# Pre_Amplifier.net
KiCad netlist of a schematic drawn in Altium Designer
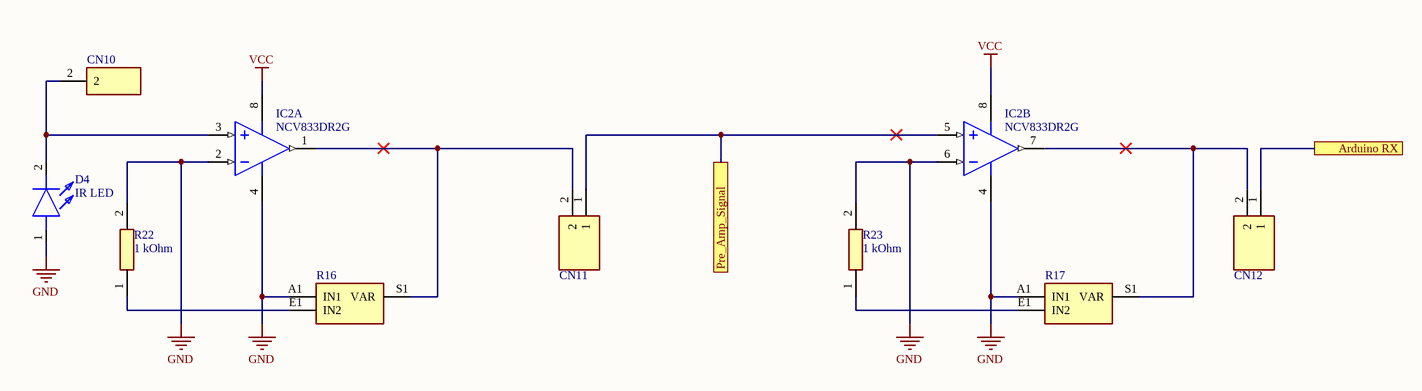
[diagram p0: Pre_Amplifier.SchDoc]

(export (version "E")
  (design (tool "Eeschema 10.0.6"))
  (components
    (comp (ref "CN10")
      (value "1 Pin Header")
      (footprint "1 PIN HEADER")
      (description "Connector")
      (fields
        (field (name "MANUFACTURER_PART_NUMBER") "5-146281-1")
        (field (name "MOUSER PART NUMBER") "571-5-146281-1")
      )
      (libsource (lib "IR_Communication_Schematic_Lib") (part "1 Pin Header"))
    )
    (comp (ref "CN11")
      (value "2 Pin Header")
      (footprint "2 Pin Header")
      (description "Connector")
      (fields
        (field (name "MANUFACTURER_PART_NUMBER") "5-146284-2")
        (field (name "MOUSER PART NUMBER") "571-5-146284-2")
      )
      (libsource (lib "IR_Communication_Schematic_Lib") (part "2 Pin Header"))
    )
    (comp (ref "CN12")
      (value "2 Pin Header")
      (footprint "2 Pin Header")
      (description "Connector")
      (fields
        (field (name "MANUFACTURER_PART_NUMBER") "5-146284-2")
        (field (name "MOUSER PART NUMBER") "571-5-146284-2")
      )
      (libsource (lib "IR_Communication_Schematic_Lib") (part "2 Pin Header"))
    )
    (comp (ref "D4")
      (value "IR LED")
      (footprint "SamacSys:ELIR204H16L10")
      (description "LED EL-IR204_H16_L10")
      (fields
        (field (name "MANUFACTURER_PART_NUMBER") "EL-IR204/H16/L10")
        (field (name "MOUSER PART NUMBER") "638-IR204/H16/L10")
      )
      (libsource (lib "IR_Communication_Schematic_Lib") (part "IR LED"))
    )
    (comp (ref "IC2")
      (value "NCV833DR2G")
      (footprint "Footprint Opamp")
      (description "Low Noise, Audio Dual Operational Amplifier, -40 to 85 degC, 8-Pin SOIC, Pb-Free, Tape and Reel")
      (fields (field (name "MANUFACTURER") "On Semiconductor"))
      (libsource (lib "IR_Communication_Schematic_Lib") (part "Opamp"))
    )
    (comp (ref "R16")
      (value "PT10LV10-202A2020-S")
      (footprint "Variable resistor")
      (description "Variable Resistor")
      (fields (field (name "MOUSER PART NUMBER") "531-PT10V-2K-S"))
      (libsource (lib "IR_Communication_Schematic_Lib") (part "PT10LV10-202A2020-S"))
    )
    (comp (ref "R17")
      (value "PT10LV10-202A2020-S")
      (footprint "Variable resistor")
      (description "Variable Resistor")
      (fields (field (name "MOUSER PART NUMBER") "531-PT10V-2K-S"))
      (libsource (lib "IR_Communication_Schematic_Lib") (part "PT10LV10-202A2020-S"))
    )
    (comp (ref "R22")
      (value "1 kOhm")
      (footprint "0805")
      (description "Resistor")
      (fields
        (field (name "MANUFACTURER_PART_NUMBER") "RP0805BRD071KL")
        (field (name "MOUSER PART NUMBER") "603-RP0805BRD071KL")
      )
      (libsource (lib "IR_Communication_Schematic_Lib") (part "Resistor"))
    )
    (comp (ref "R23")
      (value "1 kOhm")
      (footprint "0805")
      (description "Resistor")
      (fields
        (field (name "MANUFACTURER_PART_NUMBER") "RP0805BRD071KL")
        (field (name "MOUSER PART NUMBER") "603-RP0805BRD071KL")
      )
      (libsource (lib "IR_Communication_Schematic_Lib") (part "Resistor"))
    )
  )
  (nets
    (net (code "1") (name "/Arduino RX") (class "Default")
      (node (ref "CN12") (pin "1") (pinfunction "1_1") (pintype "passive"))
    )
    (net (code "2") (name "/Pre_Amp_Signal") (class "Default")
      (node (ref "CN11") (pin "1") (pinfunction "1_1") (pintype "passive"))
      (node (ref "IC2") (pin "5") (pinfunction "IN2+_5") (pintype "input"))
    )
    (net (code "3") (name "GND") (class "Default")
      (node (ref "D4") (pin "1") (pinfunction "A_1") (pintype "passive"))
      (node (ref "IC2") (pin "2") (pinfunction "IN1-_2") (pintype "input"))
      (node (ref "IC2") (pin "4") (pinfunction "VEE_4") (pintype "power_in"))
      (node (ref "IC2") (pin "6") (pinfunction "IN2-_6") (pintype "input"))
      (node (ref "R16") (pin "A1") (pinfunction "IN1_A1") (pintype "passive"))
      (node (ref "R17") (pin "A1") (pinfunction "IN1_A1") (pintype "passive"))
      (node (ref "R22") (pin "2") (pinfunction "2_2") (pintype "passive"))
      (node (ref "R23") (pin "2") (pinfunction "2_2") (pintype "passive"))
    )
    (net (code "4") (name "Net-(D4-K)") (class "Default")
      (node (ref "CN10") (pin "2") (pinfunction "2_2") (pintype "passive"))
      (node (ref "D4") (pin "2") (pinfunction "K_2") (pintype "passive"))
      (node (ref "IC2") (pin "3") (pinfunction "IN1+_3") (pintype "input"))
    )
    (net (code "5") (name "Net-(IC2A-OUT1)") (class "Default")
      (node (ref "CN11") (pin "2") (pinfunction "2_2") (pintype "passive"))
      (node (ref "IC2") (pin "1") (pinfunction "OUT1_1") (pintype "output"))
      (node (ref "R16") (pin "S1") (pinfunction "VAR_S1") (pintype "passive"))
    )
    (net (code "6") (name "Net-(IC2B-OUT2)") (class "Default")
      (node (ref "CN12") (pin "2") (pinfunction "2_2") (pintype "passive"))
      (node (ref "IC2") (pin "7") (pinfunction "OUT2_7") (pintype "output"))
      (node (ref "R17") (pin "S1") (pinfunction "VAR_S1") (pintype "passive"))
    )
    (net (code "7") (name "Net-(R16-IN2)") (class "Default")
      (node (ref "R16") (pin "E1") (pinfunction "IN2_E1") (pintype "passive"))
      (node (ref "R22") (pin "1") (pinfunction "1_1") (pintype "passive"))
    )
    (net (code "8") (name "Net-(R17-IN2)") (class "Default")
      (node (ref "R17") (pin "E1") (pinfunction "IN2_E1") (pintype "passive"))
      (node (ref "R23") (pin "1") (pinfunction "1_1") (pintype "passive"))
    )
    (net (code "9") (name "VCC") (class "Default")
      (node (ref "IC2") (pin "8") (pinfunction "VCC_8") (pintype "power_in"))
    )
  )
)
